# 02_CONNECTOR.net
KiCad netlist of a schematic drawn in Altium Designer
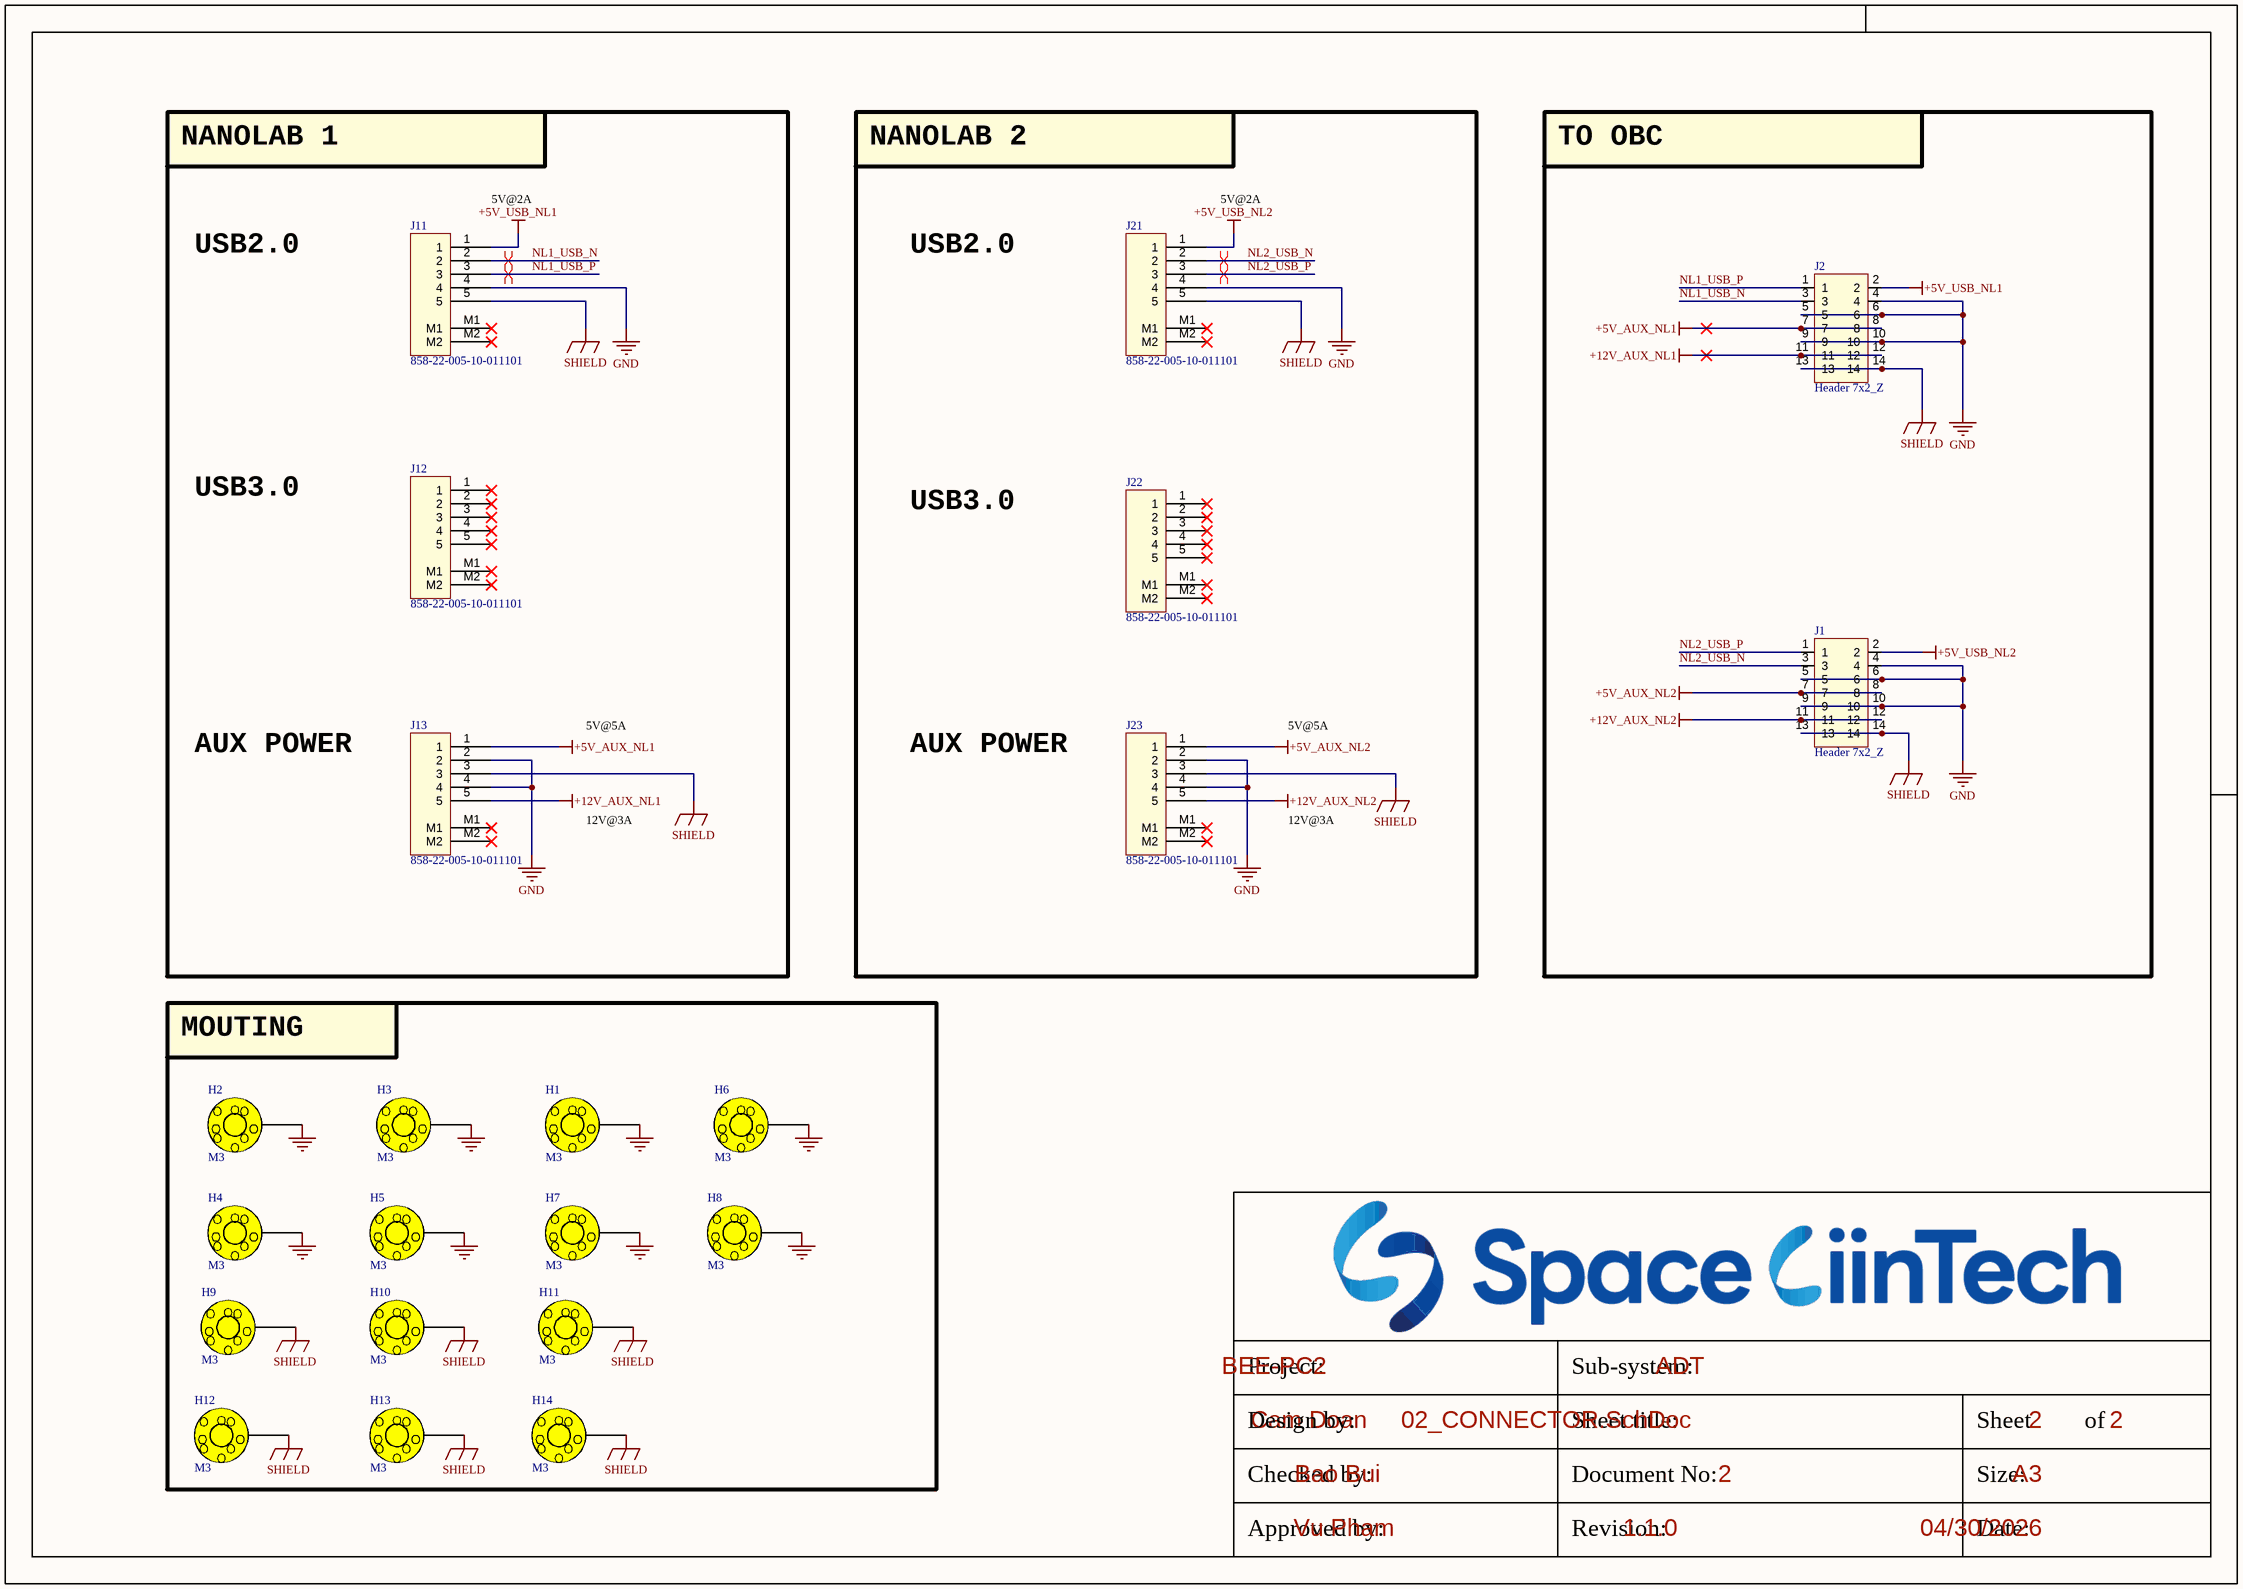
[diagram p0: 02_CONNECTOR.SchDoc]

(export (version "E")
  (design (tool "Eeschema 10.0.6"))
  (components
    (comp (ref "H1") (value "M3") (footprint "HEX-M3_NoVia") (libsource (lib "hex_M3") (part "HEX-M3")))
    (comp (ref "H2") (value "M3") (footprint "HEX-M3_NoVia") (libsource (lib "hex_M3") (part "HEX-M3")))
    (comp (ref "H3") (value "M3") (footprint "HEX-M3_NoVia") (libsource (lib "hex_M3") (part "HEX-M3")))
    (comp (ref "H4") (value "M3") (footprint "HEX-M3_NoVia") (libsource (lib "hex_M3") (part "HEX-M3")))
    (comp (ref "H5") (value "M3") (footprint "HEX-M3_NoVia") (libsource (lib "hex_M3") (part "HEX-M3")))
    (comp (ref "H6") (value "M3") (footprint "HEX-M3_NoVia") (libsource (lib "hex_M3") (part "HEX-M3")))
    (comp (ref "H7") (value "M3") (footprint "HEX-M3_NoVia") (libsource (lib "hex_M3") (part "HEX-M3")))
    (comp (ref "H8") (value "M3") (footprint "HEX-M3_NoVia") (libsource (lib "hex_M3") (part "HEX-M3")))
    (comp (ref "H9") (value "M3") (footprint "HEX-M3_NoVia") (libsource (lib "hex_M3") (part "HEX-M3")))
    (comp (ref "H10") (value "M3") (footprint "HEX-M3_NoVia") (libsource (lib "hex_M3") (part "HEX-M3")))
    (comp (ref "H11") (value "M3") (footprint "HEX-M3_NoVia") (libsource (lib "hex_M3") (part "HEX-M3")))
    (comp (ref "H12") (value "M3") (footprint "HEX-M3_NoVia") (libsource (lib "hex_M3") (part "HEX-M3")))
    (comp (ref "H13") (value "M3") (footprint "HEX-M3_NoVia") (libsource (lib "hex_M3") (part "HEX-M3")))
    (comp (ref "H14") (value "M3") (footprint "HEX-M3_NoVia") (libsource (lib "hex_M3") (part "HEX-M3")))
    (comp (ref "J1")
      (value "Header 7x2_Z")
      (footprint "SAMTEC_TSW-107-07-F-D")
      (libsource (lib "LABLIB") (part "Header 7x2_Z"))
    )
    (comp (ref "J2")
      (value "Header 7x2_Z")
      (footprint "SAMTEC_TSW-107-07-F-D")
      (libsource (lib "LABLIB") (part "Header 7x2_Z"))
    )
    (comp (ref "J11")
      (value "858-22-005-10-011101")
      (footprint "Mill-Max_858-22-005-10-011101")
      (libsource (lib "LABLIB") (part "Header 5x1_2M"))
    )
    (comp (ref "J12")
      (value "858-22-005-10-011101")
      (footprint "Mill-Max_858-22-005-10-011101")
      (libsource (lib "LABLIB") (part "Header 5x1_2M"))
    )
    (comp (ref "J13")
      (value "858-22-005-10-011101")
      (footprint "Mill-Max_858-22-005-10-011101")
      (libsource (lib "LABLIB") (part "Header 5x1_2M"))
    )
    (comp (ref "J21")
      (value "858-22-005-10-011101")
      (footprint "Mill-Max_858-22-005-10-011101")
      (libsource (lib "LABLIB") (part "Header 5x1_2M"))
    )
    (comp (ref "J22")
      (value "858-22-005-10-011101")
      (footprint "Mill-Max_858-22-005-10-011101")
      (libsource (lib "LABLIB") (part "Header 5x1_2M"))
    )
    (comp (ref "J23")
      (value "858-22-005-10-011101")
      (footprint "Mill-Max_858-22-005-10-011101")
      (libsource (lib "LABLIB") (part "Header 5x1_2M"))
    )
  )
  (nets
    (net (code "1") (name "+5V_AUX_NL1") (class "Default")
      (node (ref "J13") (pin "1") (pinfunction "1_1") (pintype "passive"))
      (node (ref "J2") (pin "7") (pinfunction "7_7") (pintype "passive"))
      (node (ref "J2") (pin "8") (pinfunction "8_8") (pintype "passive"))
    )
    (net (code "2") (name "+5V_AUX_NL2") (class "Default")
      (node (ref "J1") (pin "7") (pinfunction "7_7") (pintype "passive"))
      (node (ref "J1") (pin "8") (pinfunction "8_8") (pintype "passive"))
      (node (ref "J23") (pin "1") (pinfunction "1_1") (pintype "passive"))
    )
    (net (code "3") (name "+5V_USB_NL1") (class "Default")
      (node (ref "J11") (pin "1") (pinfunction "1_1") (pintype "passive"))
      (node (ref "J2") (pin "2") (pinfunction "2_2") (pintype "passive"))
    )
    (net (code "4") (name "+5V_USB_NL2") (class "Default")
      (node (ref "J1") (pin "2") (pinfunction "2_2") (pintype "passive"))
      (node (ref "J21") (pin "1") (pinfunction "1_1") (pintype "passive"))
    )
    (net (code "5") (name "+12V_AUX_NL1") (class "Default")
      (node (ref "J13") (pin "5") (pinfunction "5_5") (pintype "passive"))
      (node (ref "J2") (pin "11") (pinfunction "11_11") (pintype "passive"))
      (node (ref "J2") (pin "12") (pinfunction "12_12") (pintype "passive"))
    )
    (net (code "6") (name "+12V_AUX_NL2") (class "Default")
      (node (ref "J1") (pin "11") (pinfunction "11_11") (pintype "passive"))
      (node (ref "J1") (pin "12") (pinfunction "12_12") (pintype "passive"))
      (node (ref "J23") (pin "5") (pinfunction "5_5") (pintype "passive"))
    )
    (net (code "7") (name "/NL1_USB_N") (class "Default")
      (node (ref "J11") (pin "2") (pinfunction "2_2") (pintype "passive"))
      (node (ref "J2") (pin "3") (pinfunction "3_3") (pintype "passive"))
    )
    (net (code "8") (name "/NL1_USB_P") (class "Default")
      (node (ref "J11") (pin "3") (pinfunction "3_3") (pintype "passive"))
      (node (ref "J2") (pin "1") (pinfunction "1_1") (pintype "passive"))
    )
    (net (code "9") (name "/NL2_USB_N") (class "Default")
      (node (ref "J1") (pin "3") (pinfunction "3_3") (pintype "passive"))
      (node (ref "J21") (pin "2") (pinfunction "2_2") (pintype "passive"))
    )
    (net (code "10") (name "/NL2_USB_P") (class "Default")
      (node (ref "J1") (pin "1") (pinfunction "1_1") (pintype "passive"))
      (node (ref "J21") (pin "3") (pinfunction "3_3") (pintype "passive"))
    )
    (net (code "11") (name "GND") (class "Default")
      (node (ref "H1") (pin "1") (pinfunction "1_1") (pintype "power_in"))
      (node (ref "H2") (pin "1") (pinfunction "1_1") (pintype "power_in"))
      (node (ref "H3") (pin "1") (pinfunction "1_1") (pintype "power_in"))
      (node (ref "H4") (pin "1") (pinfunction "1_1") (pintype "power_in"))
      (node (ref "H5") (pin "1") (pinfunction "1_1") (pintype "power_in"))
      (node (ref "H6") (pin "1") (pinfunction "1_1") (pintype "power_in"))
      (node (ref "H7") (pin "1") (pinfunction "1_1") (pintype "power_in"))
      (node (ref "H8") (pin "1") (pinfunction "1_1") (pintype "power_in"))
      (node (ref "J1") (pin "10") (pinfunction "10_10") (pintype "passive"))
      (node (ref "J1") (pin "4") (pinfunction "4_4") (pintype "passive"))
      (node (ref "J1") (pin "5") (pinfunction "5_5") (pintype "passive"))
      (node (ref "J1") (pin "6") (pinfunction "6_6") (pintype "passive"))
      (node (ref "J1") (pin "9") (pinfunction "9_9") (pintype "passive"))
      (node (ref "J11") (pin "4") (pinfunction "4_4") (pintype "passive"))
      (node (ref "J13") (pin "2") (pinfunction "2_2") (pintype "passive"))
      (node (ref "J13") (pin "4") (pinfunction "4_4") (pintype "passive"))
      (node (ref "J2") (pin "10") (pinfunction "10_10") (pintype "passive"))
      (node (ref "J2") (pin "4") (pinfunction "4_4") (pintype "passive"))
      (node (ref "J2") (pin "5") (pinfunction "5_5") (pintype "passive"))
      (node (ref "J2") (pin "6") (pinfunction "6_6") (pintype "passive"))
      (node (ref "J2") (pin "9") (pinfunction "9_9") (pintype "passive"))
      (node (ref "J21") (pin "4") (pinfunction "4_4") (pintype "passive"))
      (node (ref "J23") (pin "2") (pinfunction "2_2") (pintype "passive"))
      (node (ref "J23") (pin "4") (pinfunction "4_4") (pintype "passive"))
    )
    (net (code "12") (name "SHIELD") (class "Default")
      (node (ref "H10") (pin "1") (pinfunction "1_1") (pintype "power_in"))
      (node (ref "H11") (pin "1") (pinfunction "1_1") (pintype "power_in"))
      (node (ref "H12") (pin "1") (pinfunction "1_1") (pintype "power_in"))
      (node (ref "H13") (pin "1") (pinfunction "1_1") (pintype "power_in"))
      (node (ref "H14") (pin "1") (pinfunction "1_1") (pintype "power_in"))
      (node (ref "H9") (pin "1") (pinfunction "1_1") (pintype "power_in"))
      (node (ref "J1") (pin "13") (pinfunction "13_13") (pintype "passive"))
      (node (ref "J1") (pin "14") (pinfunction "14_14") (pintype "passive"))
      (node (ref "J11") (pin "5") (pinfunction "5_5") (pintype "passive"))
      (node (ref "J13") (pin "3") (pinfunction "3_3") (pintype "passive"))
      (node (ref "J2") (pin "13") (pinfunction "13_13") (pintype "passive"))
      (node (ref "J2") (pin "14") (pinfunction "14_14") (pintype "passive"))
      (node (ref "J21") (pin "5") (pinfunction "5_5") (pintype "passive"))
      (node (ref "J23") (pin "3") (pinfunction "3_3") (pintype "passive"))
    )
    (net (code "13") (name "unconnected-(J11-PadM1)") (class "Default")
      (node (ref "J11") (pin "M1") (pinfunction "M1_M1") (pintype "passive+no_connect"))
    )
    (net (code "14") (name "unconnected-(J11-PadM2)") (class "Default")
      (node (ref "J11") (pin "M2") (pinfunction "M2_M2") (pintype "passive+no_connect"))
    )
    (net (code "15") (name "unconnected-(J12-Pad1)") (class "Default")
      (node (ref "J12") (pin "1") (pinfunction "1_1") (pintype "passive+no_connect"))
    )
    (net (code "16") (name "unconnected-(J12-Pad2)") (class "Default")
      (node (ref "J12") (pin "2") (pinfunction "2_2") (pintype "passive+no_connect"))
    )
    (net (code "17") (name "unconnected-(J12-Pad3)") (class "Default")
      (node (ref "J12") (pin "3") (pinfunction "3_3") (pintype "passive+no_connect"))
    )
    (net (code "18") (name "unconnected-(J12-Pad4)") (class "Default")
      (node (ref "J12") (pin "4") (pinfunction "4_4") (pintype "passive+no_connect"))
    )
    (net (code "19") (name "unconnected-(J12-Pad5)") (class "Default")
      (node (ref "J12") (pin "5") (pinfunction "5_5") (pintype "passive+no_connect"))
    )
    (net (code "20") (name "unconnected-(J12-PadM1)") (class "Default")
      (node (ref "J12") (pin "M1") (pinfunction "M1_M1") (pintype "passive+no_connect"))
    )
    (net (code "21") (name "unconnected-(J12-PadM2)") (class "Default")
      (node (ref "J12") (pin "M2") (pinfunction "M2_M2") (pintype "passive+no_connect"))
    )
    (net (code "22") (name "unconnected-(J13-PadM1)") (class "Default")
      (node (ref "J13") (pin "M1") (pinfunction "M1_M1") (pintype "passive+no_connect"))
    )
    (net (code "23") (name "unconnected-(J13-PadM2)") (class "Default")
      (node (ref "J13") (pin "M2") (pinfunction "M2_M2") (pintype "passive+no_connect"))
    )
    (net (code "24") (name "unconnected-(J21-PadM1)") (class "Default")
      (node (ref "J21") (pin "M1") (pinfunction "M1_M1") (pintype "passive+no_connect"))
    )
    (net (code "25") (name "unconnected-(J21-PadM2)") (class "Default")
      (node (ref "J21") (pin "M2") (pinfunction "M2_M2") (pintype "passive+no_connect"))
    )
    (net (code "26") (name "unconnected-(J22-Pad1)") (class "Default")
      (node (ref "J22") (pin "1") (pinfunction "1_1") (pintype "passive+no_connect"))
    )
    (net (code "27") (name "unconnected-(J22-Pad2)") (class "Default")
      (node (ref "J22") (pin "2") (pinfunction "2_2") (pintype "passive+no_connect"))
    )
    (net (code "28") (name "unconnected-(J22-Pad3)") (class "Default")
      (node (ref "J22") (pin "3") (pinfunction "3_3") (pintype "passive+no_connect"))
    )
    (net (code "29") (name "unconnected-(J22-Pad4)") (class "Default")
      (node (ref "J22") (pin "4") (pinfunction "4_4") (pintype "passive+no_connect"))
    )
    (net (code "30") (name "unconnected-(J22-Pad5)") (class "Default")
      (node (ref "J22") (pin "5") (pinfunction "5_5") (pintype "passive+no_connect"))
    )
    (net (code "31") (name "unconnected-(J22-PadM1)") (class "Default")
      (node (ref "J22") (pin "M1") (pinfunction "M1_M1") (pintype "passive+no_connect"))
    )
    (net (code "32") (name "unconnected-(J22-PadM2)") (class "Default")
      (node (ref "J22") (pin "M2") (pinfunction "M2_M2") (pintype "passive+no_connect"))
    )
    (net (code "33") (name "unconnected-(J23-PadM1)") (class "Default")
      (node (ref "J23") (pin "M1") (pinfunction "M1_M1") (pintype "passive+no_connect"))
    )
    (net (code "34") (name "unconnected-(J23-PadM2)") (class "Default")
      (node (ref "J23") (pin "M2") (pinfunction "M2_M2") (pintype "passive+no_connect"))
    )
  )
)
